# FTDI_ESP_Programmer_V1_0.net
KiCad netlist of a schematic drawn in EAGLE
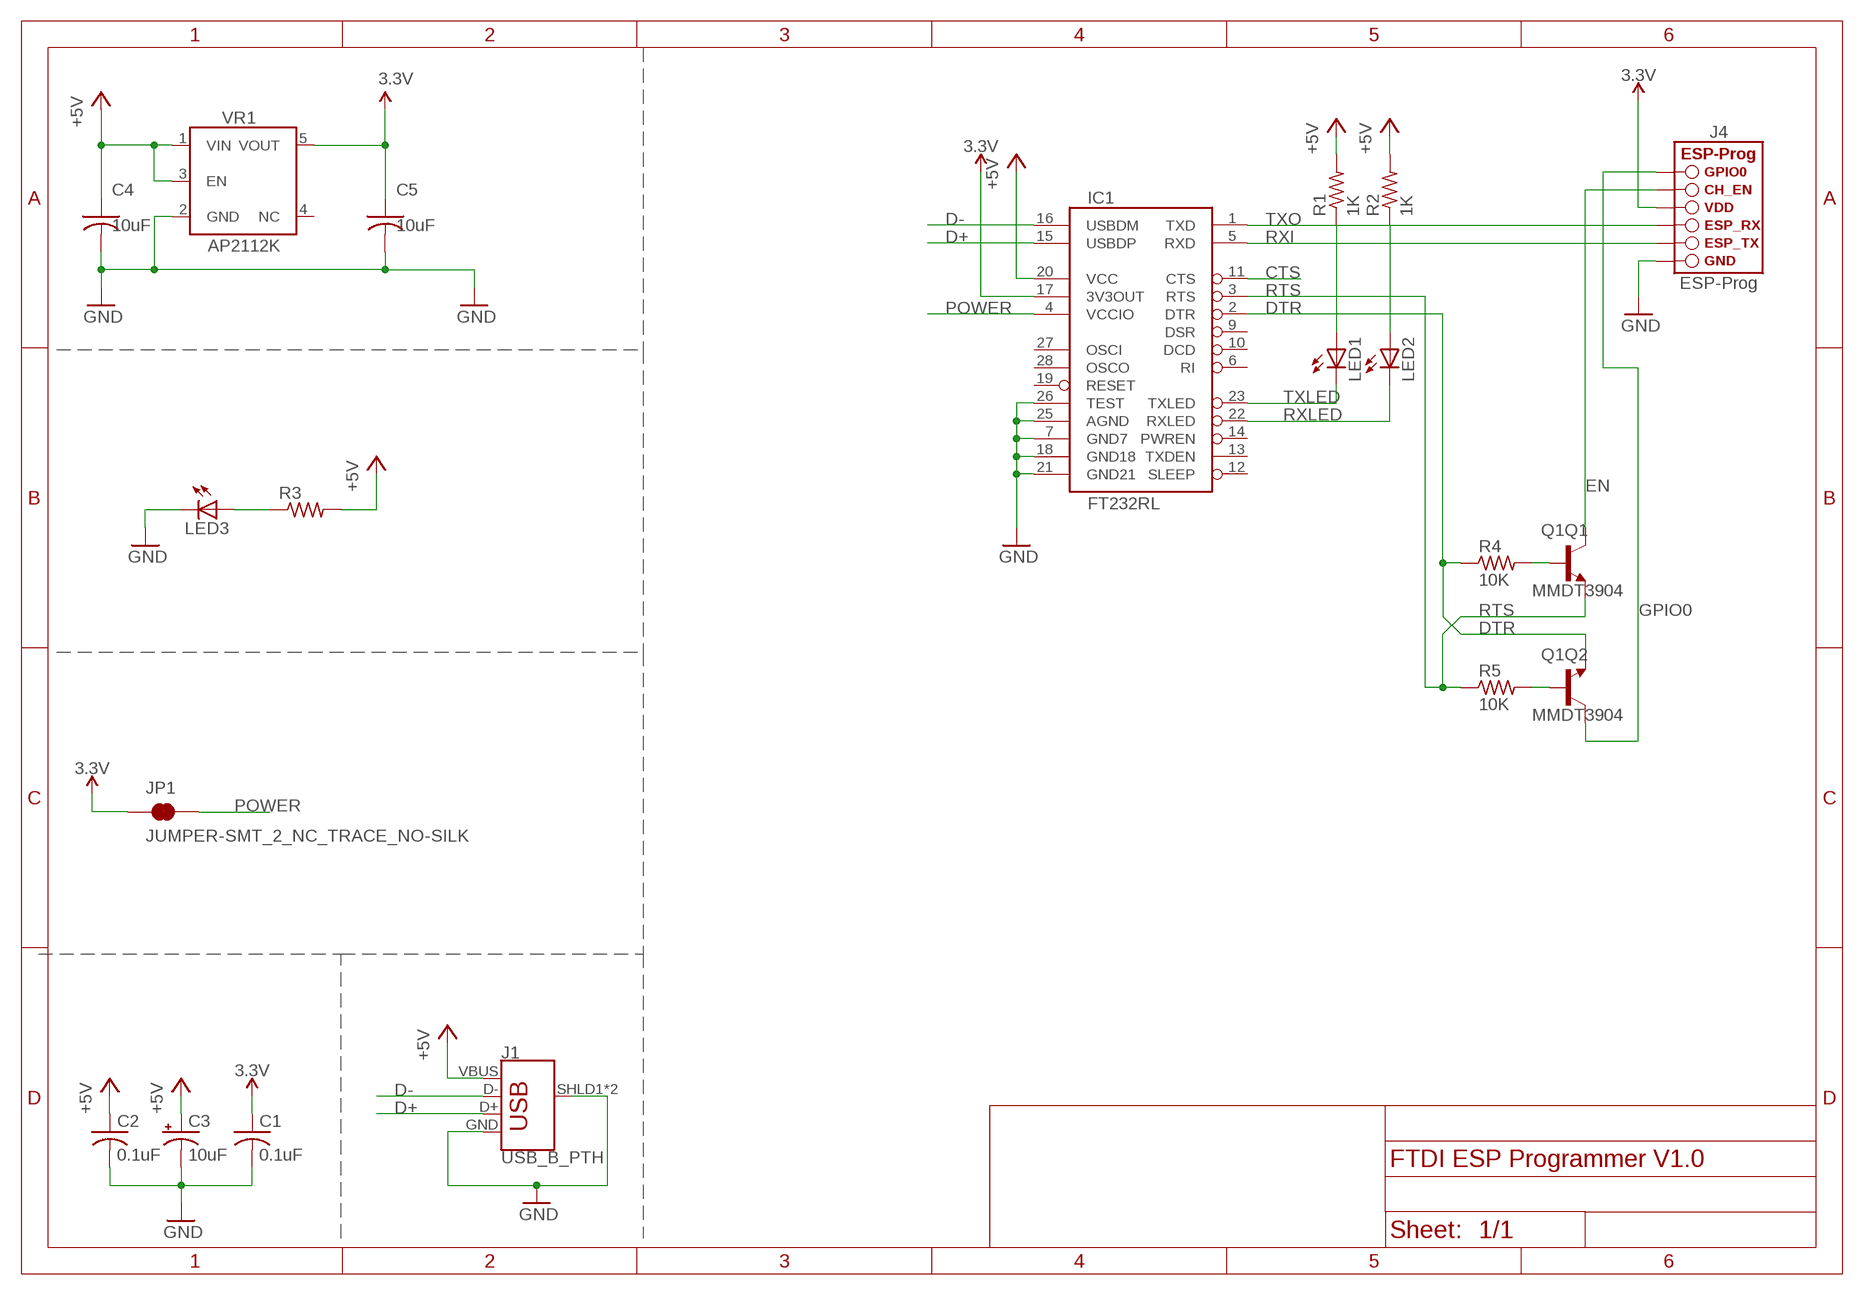
[diagram p0: schematic, sheet 1]

(export (version "E")
  (design (tool "Eeschema 10.0.6"))
  (components
    (comp (ref "C1")
      (value "0.1uF")
      (footprint "eagle-import:C0603")
      (libsource (lib "eagle-import") (part "C-USC0603"))
    )
    (comp (ref "C2")
      (value "0.1uF")
      (footprint "eagle-import:C0603")
      (libsource (lib "eagle-import") (part "C-USC0603"))
    )
    (comp (ref "C3")
      (value "10uF")
      (footprint "eagle-import:EIA3216")
      (libsource (lib "eagle-import") (part "10UF-POLAR-EIA3216-16V-10%(TANT)"))
    )
    (comp (ref "C4")
      (value "10uF")
      (footprint "eagle-import:C0603")
      (libsource (lib "eagle-import") (part "C-USC0603"))
    )
    (comp (ref "C5")
      (value "10uF")
      (footprint "eagle-import:C0603")
      (libsource (lib "eagle-import") (part "C-USC0603"))
    )
    (comp (ref "IC1")
      (value "FT232RL")
      (footprint "eagle-import:SSOP28DB")
      (libsource (lib "eagle-import") (part "FT232RLSSOP"))
    )
    (comp (ref "J1")
      (value "USB_B_PTH")
      (footprint "eagle-import:USB-B-PTH")
      (libsource (lib "eagle-import") (part "USB_B_PTH"))
    )
    (comp (ref "J4")
      (value "ESP-PROG-1X6-2.54-SOCKET-RA")
      (footprint "eagle-import:1X6-2.54-SOCKET-RA")
      (libsource (lib "eagle-import") (part "ESP-PROG-1X6-2.54-SOCKET-RA"))
    )
    (comp (ref "JP1")
      (value "JUMPER-SMT_2_NC_TRACE_NO-SILK")
      (footprint "eagle-import:SMT-JUMPER_2_NC_TRACE_NO-SILK")
      (libsource (lib "eagle-import") (part "JUMPER-SMT_2_NC_TRACE_NO-SILK"))
    )
    (comp (ref "LED1")
      (value "LEDCHIP-LED0805")
      (footprint "eagle-import:CHIP-LED0805")
      (libsource (lib "eagle-import") (part "LEDCHIP-LED0805"))
    )
    (comp (ref "LED2")
      (value "LEDCHIP-LED0805")
      (footprint "eagle-import:CHIP-LED0805")
      (libsource (lib "eagle-import") (part "LEDCHIP-LED0805"))
    )
    (comp (ref "LED3")
      (value "LEDCHIP-LED0805")
      (footprint "eagle-import:CHIP-LED0805")
      (libsource (lib "eagle-import") (part "LEDCHIP-LED0805"))
    )
    (comp (ref "Q1")
      (value "MMDT3904")
      (footprint "eagle-import:SOT-363")
      (libsource (lib "eagle-import") (part "TRANS_NPN_DUAL-MMDT3904"))
    )
    (comp (ref "R1")
      (value "1K")
      (footprint "eagle-import:R0603")
      (libsource (lib "eagle-import") (part "R-US_R0603"))
    )
    (comp (ref "R2")
      (value "1K")
      (footprint "eagle-import:R0603")
      (libsource (lib "eagle-import") (part "R-US_R0603"))
    )
    (comp (ref "R3")
      (value "R-USR0603")
      (footprint "eagle-import:R0603@1")
      (libsource (lib "eagle-import") (part "R-USR0603"))
    )
    (comp (ref "R4")
      (value "10K")
      (footprint "eagle-import:R0603@1")
      (libsource (lib "eagle-import") (part "R-USR0603"))
    )
    (comp (ref "R5")
      (value "10K")
      (footprint "eagle-import:R0603@1")
      (libsource (lib "eagle-import") (part "R-USR0603"))
    )
    (comp (ref "VR1")
      (value "AP2112KSOT25")
      (footprint "eagle-import:SOT23-5")
      (libsource (lib "eagle-import") (part "AP2112KSOT25"))
    )
  )
  (nets
    (net (code "1") (name "+5V") (class "Default")
      (node (ref "C2") (pin "1") (pinfunction "1_1") (pintype "passive"))
      (node (ref "C3") (pin "+") (pinfunction "+_+") (pintype "passive"))
      (node (ref "C4") (pin "1") (pinfunction "1_1") (pintype "passive"))
      (node (ref "IC1") (pin "20") (pinfunction "VCC_20") (pintype "power_in"))
      (node (ref "J1") (pin "VBUS") (pinfunction "VBUS_VBUS") (pintype "power_in"))
      (node (ref "R1") (pin "2") (pinfunction "2_2") (pintype "passive"))
      (node (ref "R2") (pin "2") (pinfunction "2_2") (pintype "passive"))
      (node (ref "R3") (pin "2") (pinfunction "2_2") (pintype "passive"))
      (node (ref "VR1") (pin "1") (pinfunction "VIN_1") (pintype "bidirectional"))
      (node (ref "VR1") (pin "3") (pinfunction "EN_3") (pintype "bidirectional"))
    )
    (net (code "2") (name "/CTS") (class "Default")
      (node (ref "IC1") (pin "11") (pinfunction "CTS_11") (pintype "input"))
    )
    (net (code "3") (name "/D+") (class "Default")
      (node (ref "IC1") (pin "15") (pinfunction "USBDP_15") (pintype "bidirectional"))
      (node (ref "J1") (pin "D+") (pinfunction "D+_D+") (pintype "bidirectional"))
    )
    (net (code "4") (name "/D-") (class "Default")
      (node (ref "IC1") (pin "16") (pinfunction "USBDM_16") (pintype "bidirectional"))
      (node (ref "J1") (pin "D-") (pinfunction "D-_D-") (pintype "bidirectional"))
    )
    (net (code "5") (name "/DTR") (class "Default")
      (node (ref "IC1") (pin "2") (pinfunction "DTR_2") (pintype "output"))
      (node (ref "Q1") (pin "1") (pinfunction "E_1") (pintype "passive"))
      (node (ref "R4") (pin "1") (pinfunction "1_1") (pintype "passive"))
    )
    (net (code "6") (name "/EN") (class "Default")
      (node (ref "J4") (pin "5") (pinfunction "CH_EN_5") (pintype "passive"))
      (node (ref "Q1") (pin "3") (pinfunction "C_3") (pintype "passive"))
    )
    (net (code "7") (name "/GPIO0") (class "Default")
      (node (ref "J4") (pin "6") (pinfunction "GPIO0_6") (pintype "passive"))
      (node (ref "Q1") (pin "6") (pinfunction "C_6") (pintype "passive"))
    )
    (net (code "8") (name "/POWER") (class "Default")
      (node (ref "IC1") (pin "4") (pinfunction "VCCIO_4") (pintype "power_in"))
      (node (ref "JP1") (pin "2") (pinfunction "2_2") (pintype "passive"))
    )
    (net (code "9") (name "/RTS") (class "Default")
      (node (ref "IC1") (pin "3") (pinfunction "RTS_3") (pintype "output"))
      (node (ref "Q1") (pin "4") (pinfunction "E_4") (pintype "passive"))
      (node (ref "R5") (pin "1") (pinfunction "1_1") (pintype "passive"))
    )
    (net (code "10") (name "/RXI") (class "Default")
      (node (ref "IC1") (pin "5") (pinfunction "RXD_5") (pintype "input"))
      (node (ref "J4") (pin "2") (pinfunction "ESP_TX_2") (pintype "passive"))
    )
    (net (code "11") (name "/RXLED") (class "Default")
      (node (ref "IC1") (pin "22") (pinfunction "RXLED_22") (pintype "input"))
      (node (ref "LED2") (pin "C") (pinfunction "C_C") (pintype "passive"))
    )
    (net (code "12") (name "/TXLED") (class "Default")
      (node (ref "IC1") (pin "23") (pinfunction "TXLED_23") (pintype "input"))
      (node (ref "LED1") (pin "C") (pinfunction "C_C") (pintype "passive"))
    )
    (net (code "13") (name "/TXO") (class "Default")
      (node (ref "IC1") (pin "1") (pinfunction "TXD_1") (pintype "output"))
      (node (ref "J4") (pin "3") (pinfunction "ESP_RX_3") (pintype "passive"))
    )
    (net (code "14") (name "3.3V") (class "Default")
      (node (ref "C1") (pin "1") (pinfunction "1_1") (pintype "passive"))
      (node (ref "C5") (pin "1") (pinfunction "1_1") (pintype "passive"))
      (node (ref "IC1") (pin "17") (pinfunction "3V3OUT_17") (pintype "output"))
      (node (ref "J4") (pin "4") (pinfunction "VDD_4") (pintype "passive"))
      (node (ref "JP1") (pin "1") (pinfunction "1_1") (pintype "passive"))
      (node (ref "VR1") (pin "5") (pinfunction "VOUT_5") (pintype "bidirectional"))
    )
    (net (code "15") (name "GND") (class "Default")
      (node (ref "C1") (pin "2") (pinfunction "2_2") (pintype "passive"))
      (node (ref "C2") (pin "2") (pinfunction "2_2") (pintype "passive"))
      (node (ref "C3") (pin "-") (pinfunction "-_-") (pintype "passive"))
      (node (ref "C4") (pin "2") (pinfunction "2_2") (pintype "passive"))
      (node (ref "C5") (pin "2") (pinfunction "2_2") (pintype "passive"))
      (node (ref "IC1") (pin "18") (pinfunction "GND18_18") (pintype "power_in"))
      (node (ref "IC1") (pin "21") (pinfunction "GND21_21") (pintype "power_in"))
      (node (ref "IC1") (pin "25") (pinfunction "AGND_25") (pintype "power_in"))
      (node (ref "IC1") (pin "26") (pinfunction "TEST_26") (pintype "input"))
      (node (ref "IC1") (pin "7") (pinfunction "GND7_7") (pintype "power_in"))
      (node (ref "J1") (pin "GND") (pinfunction "GND_GND") (pintype "power_in"))
      (node (ref "J1") (pin "SHLD1") (pinfunction "SHIELD_SHLD1") (pintype "bidirectional"))
      (node (ref "J1") (pin "SHLD2") (pinfunction "SHIELD_SHLD2") (pintype "bidirectional"))
      (node (ref "J4") (pin "1") (pinfunction "GND_1") (pintype "passive"))
      (node (ref "LED3") (pin "C") (pinfunction "C_C") (pintype "passive"))
      (node (ref "VR1") (pin "2") (pinfunction "GND_2") (pintype "bidirectional"))
    )
    (net (code "16") (name "Net-(LED1-PadA)") (class "Default")
      (node (ref "LED1") (pin "A") (pinfunction "A_A") (pintype "passive"))
      (node (ref "R1") (pin "1") (pinfunction "1_1") (pintype "passive"))
    )
    (net (code "17") (name "Net-(LED2-PadA)") (class "Default")
      (node (ref "LED2") (pin "A") (pinfunction "A_A") (pintype "passive"))
      (node (ref "R2") (pin "1") (pinfunction "1_1") (pintype "passive"))
    )
    (net (code "18") (name "Net-(LED3-PadA)") (class "Default")
      (node (ref "LED3") (pin "A") (pinfunction "A_A") (pintype "passive"))
      (node (ref "R3") (pin "1") (pinfunction "1_1") (pintype "passive"))
    )
    (net (code "19") (name "Net-(Q1A-B)") (class "Default")
      (node (ref "Q1") (pin "5") (pinfunction "B_5") (pintype "passive"))
      (node (ref "R4") (pin "2") (pinfunction "2_2") (pintype "passive"))
    )
    (net (code "20") (name "Net-(Q1B-B)") (class "Default")
      (node (ref "Q1") (pin "2") (pinfunction "B_2") (pintype "passive"))
      (node (ref "R5") (pin "2") (pinfunction "2_2") (pintype "passive"))
    )
    (net (code "21") (name "unconnected-(IC1-DCD-Pad10)") (class "Default")
      (node (ref "IC1") (pin "10") (pinfunction "DCD_10") (pintype "input"))
    )
    (net (code "22") (name "unconnected-(IC1-DSR-Pad9)") (class "Default")
      (node (ref "IC1") (pin "9") (pinfunction "DSR_9") (pintype "input"))
    )
    (net (code "23") (name "unconnected-(IC1-OSCI-Pad27)") (class "Default")
      (node (ref "IC1") (pin "27") (pinfunction "OSCI_27") (pintype "input"))
    )
    (net (code "24") (name "unconnected-(IC1-OSCO-Pad28)") (class "Default")
      (node (ref "IC1") (pin "28") (pinfunction "OSCO_28") (pintype "output"))
    )
    (net (code "25") (name "unconnected-(IC1-PWREN-Pad14)") (class "Default")
      (node (ref "IC1") (pin "14") (pinfunction "PWREN_14") (pintype "input"))
    )
    (net (code "26") (name "unconnected-(IC1-RESET-Pad19)") (class "Default")
      (node (ref "IC1") (pin "19") (pinfunction "RESET_19") (pintype "input"))
    )
    (net (code "27") (name "unconnected-(IC1-RI-Pad6)") (class "Default")
      (node (ref "IC1") (pin "6") (pinfunction "RI_6") (pintype "input"))
    )
    (net (code "28") (name "unconnected-(IC1-SLEEP-Pad12)") (class "Default")
      (node (ref "IC1") (pin "12") (pinfunction "SLEEP_12") (pintype "input"))
    )
    (net (code "29") (name "unconnected-(IC1-TXDEN-Pad13)") (class "Default")
      (node (ref "IC1") (pin "13") (pinfunction "TXDEN_13") (pintype "input"))
    )
    (net (code "30") (name "unconnected-(VR1-NC-Pad4)") (class "Default")
      (node (ref "VR1") (pin "4") (pinfunction "NC_4") (pintype "bidirectional"))
    )
  )
)
